# adb.net
KiCad netlist of a schematic drawn in EAGLE
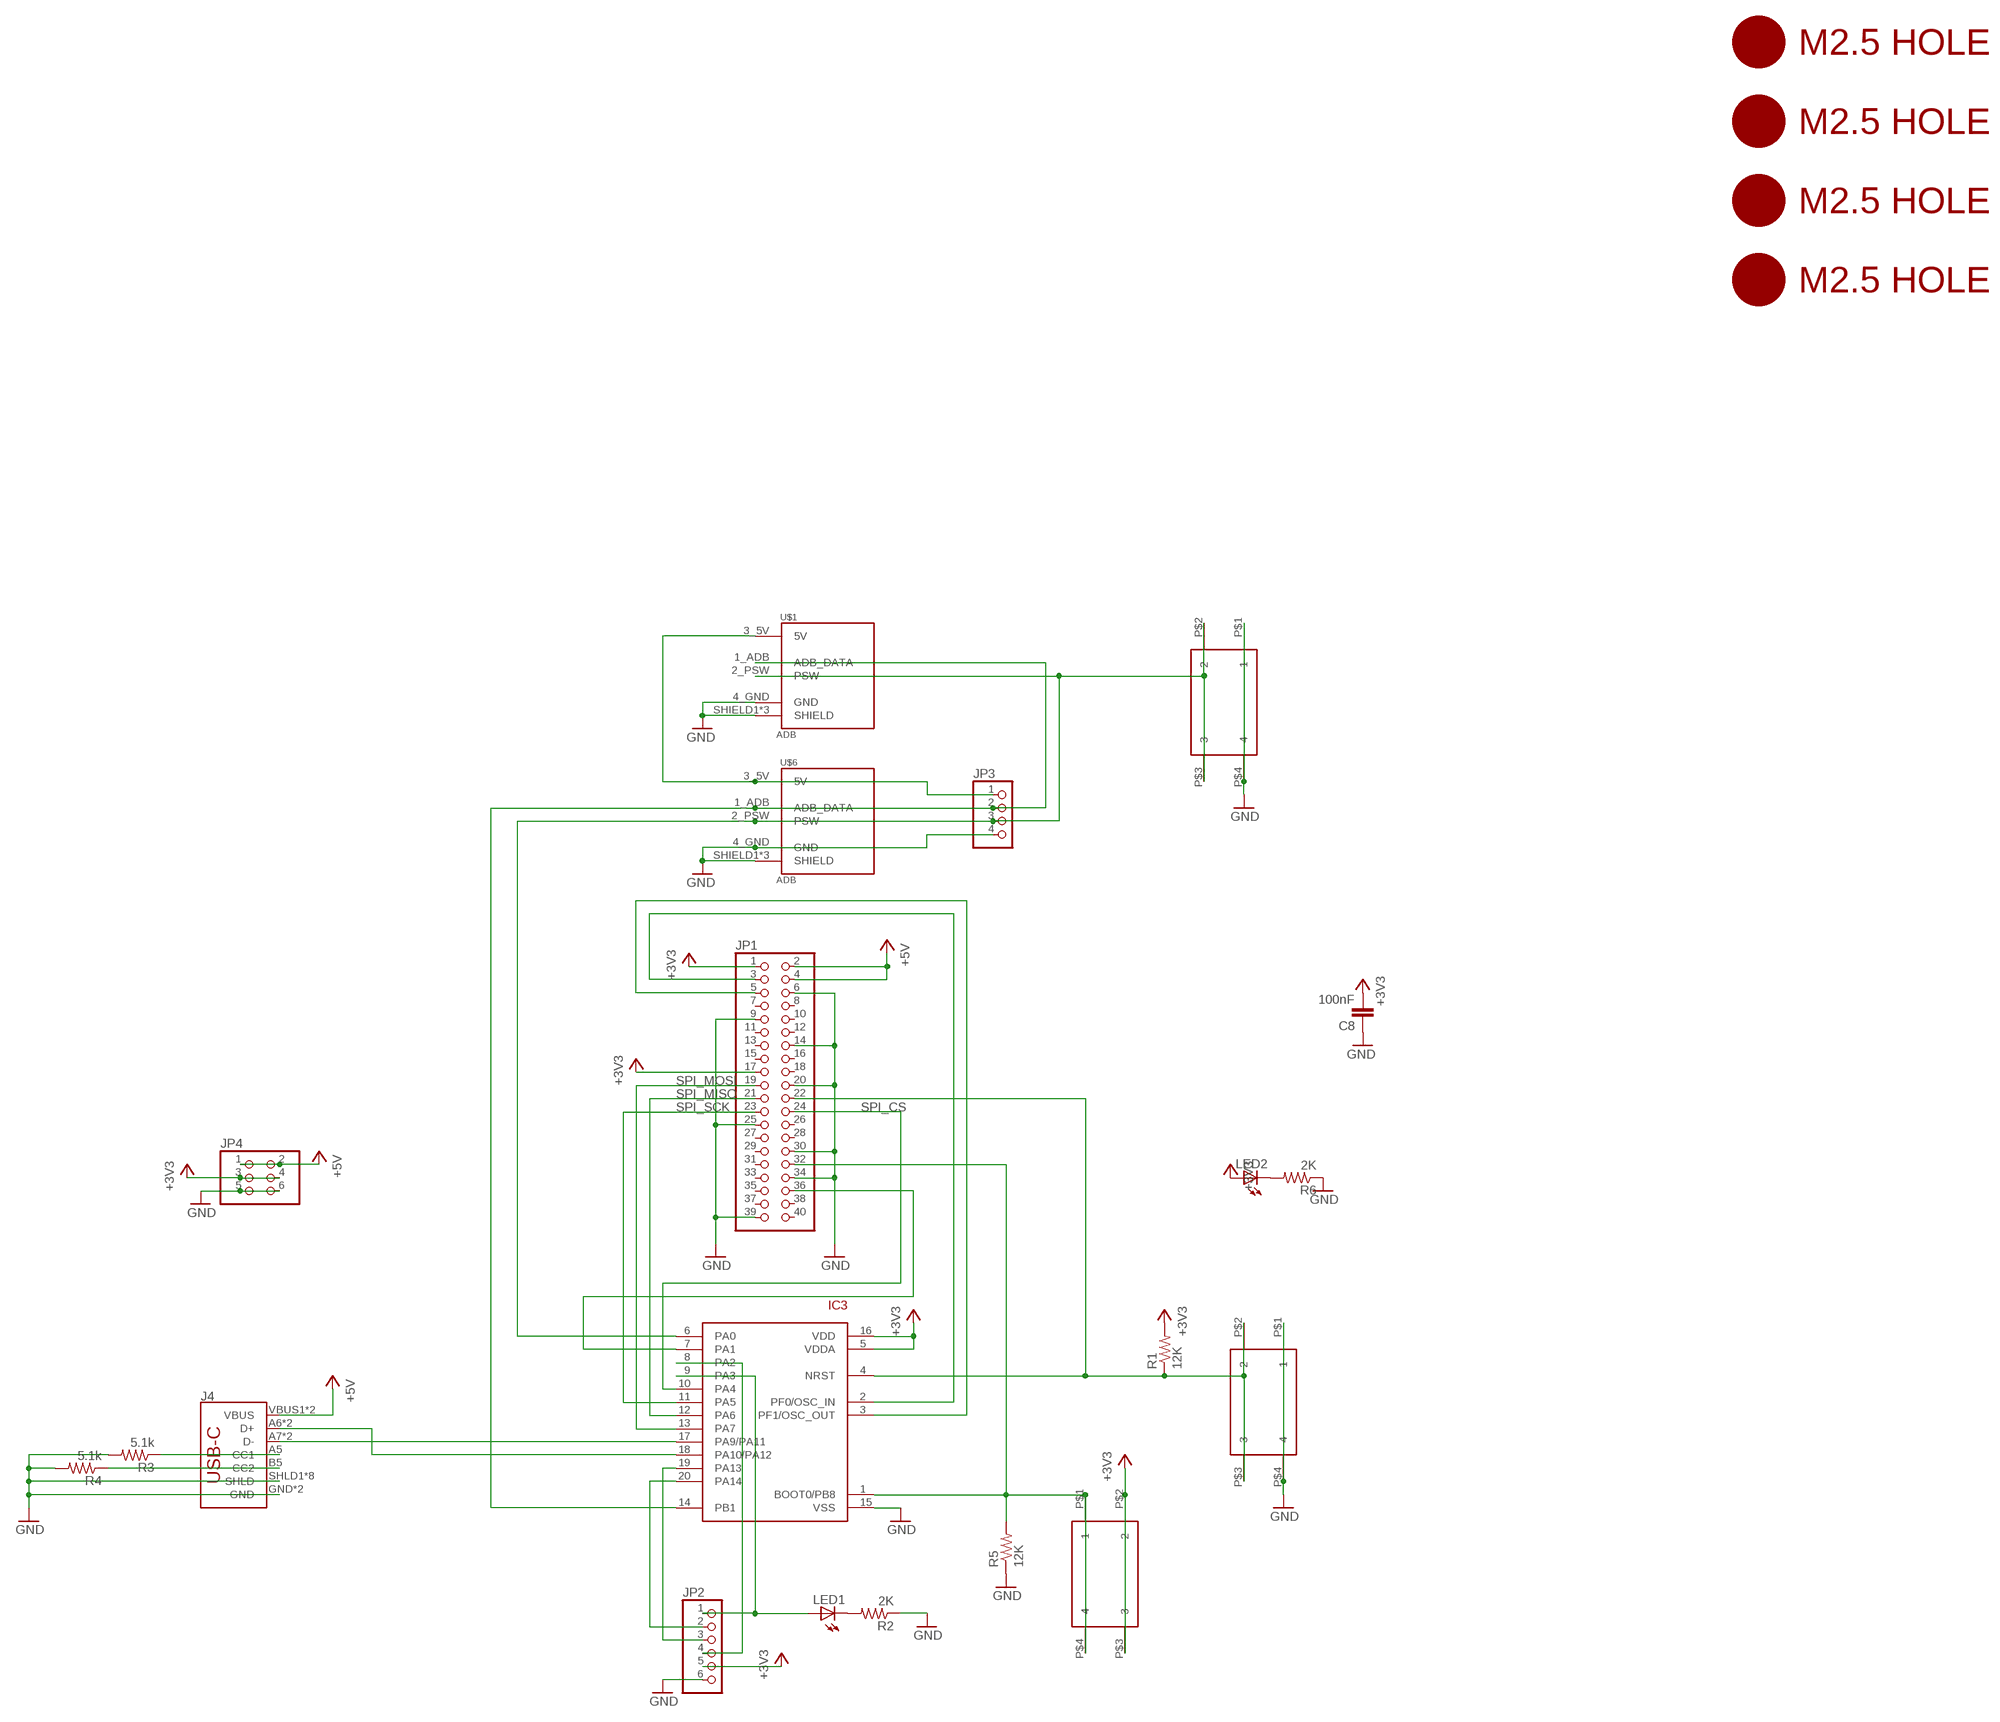
[diagram p0: schematic, sheet 1]

(export (version "E")
  (design (tool "Eeschema 10.0.6"))
  (components
    (comp (ref "C8")
      (value "100nF")
      (footprint "eagle-import:0805@1")
      (libsource (lib "eagle-import") (part "CAP0805"))
    )
    (comp (ref "IC3")
      (value "STM32F042F4")
      (footprint "eagle-import:TSSOP20")
      (libsource (lib "eagle-import") (part "STM32F042F4"))
    )
    (comp (ref "J4")
      (value "USB_C16PIN")
      (footprint "eagle-import:USB-C-16P")
      (libsource (lib "eagle-import") (part "USB_C16PIN"))
    )
    (comp (ref "JP1")
      (value "PINHD-2X20-BIG")
      (footprint "eagle-import:2X20-BIG")
      (libsource (lib "eagle-import") (part "PINHD-2X20-BIG"))
    )
    (comp (ref "JP2")
      (value "PINHD-1X6")
      (footprint "eagle-import:1X06")
      (libsource (lib "eagle-import") (part "PINHD-1X6"))
    )
    (comp (ref "JP3")
      (value "PINHD-1X4")
      (footprint "eagle-import:1X04")
      (libsource (lib "eagle-import") (part "PINHD-1X4"))
    )
    (comp (ref "JP4")
      (value "PINHD-2X3")
      (footprint "eagle-import:2X03")
      (libsource (lib "eagle-import") (part "PINHD-2X3"))
    )
    (comp (ref "LED1")
      (value "LEDCHIP-LED0805")
      (footprint "eagle-import:CHIP-LED0805")
      (libsource (lib "eagle-import") (part "LEDCHIP-LED0805"))
    )
    (comp (ref "LED2")
      (value "LEDCHIP-LED0805")
      (footprint "eagle-import:CHIP-LED0805")
      (libsource (lib "eagle-import") (part "LEDCHIP-LED0805"))
    )
    (comp (ref "R1")
      (value "12K")
      (footprint "eagle-import:0805")
      (libsource (lib "eagle-import") (part "RESISTOR0805-RES"))
    )
    (comp (ref "R2")
      (value "2K")
      (footprint "eagle-import:0805")
      (libsource (lib "eagle-import") (part "RESISTOR0805-RES"))
    )
    (comp (ref "R3")
      (value "5.1k")
      (footprint "eagle-import:0805")
      (libsource (lib "eagle-import") (part "RESISTOR0805-RES"))
    )
    (comp (ref "R4")
      (value "5.1k")
      (footprint "eagle-import:0805")
      (libsource (lib "eagle-import") (part "RESISTOR0805-RES"))
    )
    (comp (ref "R5")
      (value "12K")
      (footprint "eagle-import:0805")
      (libsource (lib "eagle-import") (part "RESISTOR0805-RES"))
    )
    (comp (ref "R6")
      (value "2K")
      (footprint "eagle-import:0805")
      (libsource (lib "eagle-import") (part "RESISTOR0805-RES"))
    )
    (comp (ref "SW1")
      (value "324_SW")
      (footprint "eagle-import:342_SWICH_FOOT")
      (libsource (lib "eagle-import") (part "324_SW"))
    )
    (comp (ref "SW2")
      (value "324_SW")
      (footprint "eagle-import:342_SWICH_FOOT")
      (libsource (lib "eagle-import") (part "324_SW"))
    )
    (comp (ref "SW4")
      (value "324_SW")
      (footprint "eagle-import:342_SWICH_FOOT")
      (libsource (lib "eagle-import") (part "324_SW"))
    )
    (comp (ref "U$1")
      (value "ADB")
      (footprint "eagle-import:DIN4")
      (libsource (lib "eagle-import") (part "ADB"))
    )
    (comp (ref "U$2")
      (value "M2.5HOLE")
      (footprint "eagle-import:M2.5HOLE")
      (libsource (lib "eagle-import") (part "M2.5HOLE"))
    )
    (comp (ref "U$3")
      (value "M2.5HOLE")
      (footprint "eagle-import:M2.5HOLE")
      (libsource (lib "eagle-import") (part "M2.5HOLE"))
    )
    (comp (ref "U$4")
      (value "M2.5HOLE")
      (footprint "eagle-import:M2.5HOLE")
      (libsource (lib "eagle-import") (part "M2.5HOLE"))
    )
    (comp (ref "U$5")
      (value "M2.5HOLE")
      (footprint "eagle-import:M2.5HOLE")
      (libsource (lib "eagle-import") (part "M2.5HOLE"))
    )
    (comp (ref "U$6")
      (value "ADB")
      (footprint "eagle-import:DIN4")
      (libsource (lib "eagle-import") (part "ADB"))
    )
  )
  (nets
    (net (code "1") (name "+3V3") (class "Default")
      (node (ref "C8") (pin "2") (pinfunction "2_2") (pintype "passive"))
      (node (ref "IC3") (pin "16") (pinfunction "VDD_16") (pintype "bidirectional"))
      (node (ref "IC3") (pin "5") (pinfunction "VDDA_5") (pintype "bidirectional"))
      (node (ref "JP1") (pin "1") (pinfunction "1_1") (pintype "passive"))
      (node (ref "JP1") (pin "17") (pinfunction "17_17") (pintype "passive"))
      (node (ref "JP2") (pin "5") (pinfunction "5_5") (pintype "passive"))
      (node (ref "JP4") (pin "3") (pinfunction "3_3") (pintype "passive"))
      (node (ref "JP4") (pin "4") (pinfunction "4_4") (pintype "passive"))
      (node (ref "LED2") (pin "A") (pinfunction "A_A") (pintype "passive"))
      (node (ref "R1") (pin "2") (pinfunction "2_2") (pintype "passive"))
      (node (ref "SW1") (pin "P$2") (pinfunction "2_P$2") (pintype "bidirectional"))
      (node (ref "SW1") (pin "P$3") (pinfunction "3_P$3") (pintype "bidirectional"))
    )
    (net (code "2") (name "+5V") (class "Default")
      (node (ref "J4") (pin "VBUS1") (pinfunction "VBUS_VBUS1") (pintype "bidirectional"))
      (node (ref "J4") (pin "VBUS2") (pinfunction "VBUS_VBUS2") (pintype "bidirectional"))
      (node (ref "JP1") (pin "2") (pinfunction "2_2") (pintype "passive"))
      (node (ref "JP1") (pin "4") (pinfunction "4_4") (pintype "passive"))
      (node (ref "JP4") (pin "1") (pinfunction "1_1") (pintype "passive"))
      (node (ref "JP4") (pin "2") (pinfunction "2_2") (pintype "passive"))
    )
    (net (code "3") (name "/SPI_CS") (class "Default")
      (node (ref "IC3") (pin "10") (pinfunction "PA4_10") (pintype "bidirectional"))
      (node (ref "JP1") (pin "24") (pinfunction "24_24") (pintype "passive"))
    )
    (net (code "4") (name "/SPI_MISO") (class "Default")
      (node (ref "IC3") (pin "12") (pinfunction "PA6_12") (pintype "bidirectional"))
      (node (ref "JP1") (pin "21") (pinfunction "21_21") (pintype "passive"))
    )
    (net (code "5") (name "/SPI_MOSI") (class "Default")
      (node (ref "IC3") (pin "13") (pinfunction "PA7_13") (pintype "bidirectional"))
      (node (ref "JP1") (pin "19") (pinfunction "19_19") (pintype "passive"))
    )
    (net (code "6") (name "/SPI_SCK") (class "Default")
      (node (ref "IC3") (pin "11") (pinfunction "PA5_11") (pintype "bidirectional"))
      (node (ref "JP1") (pin "23") (pinfunction "23_23") (pintype "passive"))
    )
    (net (code "7") (name "GND") (class "Default")
      (node (ref "C8") (pin "1") (pinfunction "1_1") (pintype "passive"))
      (node (ref "IC3") (pin "15") (pinfunction "VSS_15") (pintype "bidirectional"))
      (node (ref "J4") (pin "GND") (pinfunction "GND_GND") (pintype "bidirectional"))
      (node (ref "J4") (pin "GND2") (pinfunction "GND_GND2") (pintype "bidirectional"))
      (node (ref "J4") (pin "SHLD1") (pinfunction "SHLD_SHLD1") (pintype "bidirectional"))
      (node (ref "J4") (pin "SHLD2") (pinfunction "SHLD_SHLD2") (pintype "bidirectional"))
      (node (ref "J4") (pin "SHLD3") (pinfunction "SHLD_SHLD3") (pintype "bidirectional"))
      (node (ref "J4") (pin "SHLD4") (pinfunction "SHLD_SHLD4") (pintype "bidirectional"))
      (node (ref "J4") (pin "SHLD5") (pinfunction "SHLD_SHLD5") (pintype "bidirectional"))
      (node (ref "J4") (pin "SHLD6") (pinfunction "SHLD_SHLD6") (pintype "bidirectional"))
      (node (ref "J4") (pin "SHLD7") (pinfunction "SHLD_SHLD7") (pintype "bidirectional"))
      (node (ref "J4") (pin "SHLD8") (pinfunction "SHLD_SHLD8") (pintype "bidirectional"))
      (node (ref "JP1") (pin "14") (pinfunction "14_14") (pintype "passive"))
      (node (ref "JP1") (pin "20") (pinfunction "20_20") (pintype "passive"))
      (node (ref "JP1") (pin "25") (pinfunction "25_25") (pintype "passive"))
      (node (ref "JP1") (pin "30") (pinfunction "30_30") (pintype "passive"))
      (node (ref "JP1") (pin "34") (pinfunction "34_34") (pintype "passive"))
      (node (ref "JP1") (pin "39") (pinfunction "39_39") (pintype "passive"))
      (node (ref "JP1") (pin "6") (pinfunction "6_6") (pintype "passive"))
      (node (ref "JP1") (pin "9") (pinfunction "9_9") (pintype "passive"))
      (node (ref "JP2") (pin "6") (pinfunction "6_6") (pintype "passive"))
      (node (ref "JP3") (pin "4") (pinfunction "4_4") (pintype "passive"))
      (node (ref "JP4") (pin "5") (pinfunction "5_5") (pintype "passive"))
      (node (ref "JP4") (pin "6") (pinfunction "6_6") (pintype "passive"))
      (node (ref "R2") (pin "1") (pinfunction "1_1") (pintype "passive"))
      (node (ref "R3") (pin "2") (pinfunction "2_2") (pintype "passive"))
      (node (ref "R4") (pin "2") (pinfunction "2_2") (pintype "passive"))
      (node (ref "R5") (pin "1") (pinfunction "1_1") (pintype "passive"))
      (node (ref "R6") (pin "1") (pinfunction "1_1") (pintype "passive"))
      (node (ref "SW2") (pin "P$1") (pinfunction "1_P$1") (pintype "bidirectional"))
      (node (ref "SW2") (pin "P$4") (pinfunction "4_P$4") (pintype "bidirectional"))
      (node (ref "SW4") (pin "P$1") (pinfunction "1_P$1") (pintype "bidirectional"))
      (node (ref "SW4") (pin "P$4") (pinfunction "4_P$4") (pintype "bidirectional"))
      (node (ref "U$1") (pin "4_GND") (pinfunction "GND_4_GND") (pintype "bidirectional"))
      (node (ref "U$1") (pin "SHIELD1") (pinfunction "SHIELD_SHIELD1") (pintype "bidirectional"))
      (node (ref "U$1") (pin "SHIELD2") (pinfunction "SHIELD_SHIELD2") (pintype "bidirectional"))
      (node (ref "U$1") (pin "SHIELD3") (pinfunction "SHIELD_SHIELD3") (pintype "bidirectional"))
      (node (ref "U$6") (pin "4_GND") (pinfunction "GND_4_GND") (pintype "bidirectional"))
      (node (ref "U$6") (pin "SHIELD1") (pinfunction "SHIELD_SHIELD1") (pintype "bidirectional"))
      (node (ref "U$6") (pin "SHIELD2") (pinfunction "SHIELD_SHIELD2") (pintype "bidirectional"))
      (node (ref "U$6") (pin "SHIELD3") (pinfunction "SHIELD_SHIELD3") (pintype "bidirectional"))
    )
    (net (code "8") (name "Net-(IC3-BOOT0{slash}PB8)") (class "Default")
      (node (ref "IC3") (pin "1") (pinfunction "BOOT0/PB8_1") (pintype "bidirectional"))
      (node (ref "JP1") (pin "32") (pinfunction "32_32") (pintype "passive"))
      (node (ref "R5") (pin "2") (pinfunction "2_2") (pintype "passive"))
      (node (ref "SW1") (pin "P$1") (pinfunction "1_P$1") (pintype "bidirectional"))
      (node (ref "SW1") (pin "P$4") (pinfunction "4_P$4") (pintype "bidirectional"))
    )
    (net (code "9") (name "Net-(IC3-NRST)") (class "Default")
      (node (ref "IC3") (pin "4") (pinfunction "NRST_4") (pintype "bidirectional"))
      (node (ref "JP1") (pin "22") (pinfunction "22_22") (pintype "passive"))
      (node (ref "R1") (pin "1") (pinfunction "1_1") (pintype "passive"))
      (node (ref "SW4") (pin "P$2") (pinfunction "2_P$2") (pintype "bidirectional"))
      (node (ref "SW4") (pin "P$3") (pinfunction "3_P$3") (pintype "bidirectional"))
    )
    (net (code "10") (name "Net-(IC3-PA0)") (class "Default")
      (node (ref "IC3") (pin "6") (pinfunction "PA0_6") (pintype "bidirectional"))
      (node (ref "JP3") (pin "3") (pinfunction "3_3") (pintype "passive"))
      (node (ref "SW2") (pin "P$2") (pinfunction "2_P$2") (pintype "bidirectional"))
      (node (ref "SW2") (pin "P$3") (pinfunction "3_P$3") (pintype "bidirectional"))
      (node (ref "U$1") (pin "2_PSW") (pinfunction "PSW_2_PSW") (pintype "bidirectional"))
      (node (ref "U$6") (pin "2_PSW") (pinfunction "PSW_2_PSW") (pintype "bidirectional"))
    )
    (net (code "11") (name "Net-(IC3-PA1)") (class "Default")
      (node (ref "IC3") (pin "7") (pinfunction "PA1_7") (pintype "bidirectional"))
      (node (ref "JP1") (pin "36") (pinfunction "36_36") (pintype "passive"))
    )
    (net (code "12") (name "Net-(IC3-PA2)") (class "Default")
      (node (ref "IC3") (pin "8") (pinfunction "PA2_8") (pintype "bidirectional"))
      (node (ref "JP2") (pin "4") (pinfunction "4_4") (pintype "passive"))
    )
    (net (code "13") (name "Net-(IC3-PA3)") (class "Default")
      (node (ref "IC3") (pin "9") (pinfunction "PA3_9") (pintype "bidirectional"))
      (node (ref "JP2") (pin "1") (pinfunction "1_1") (pintype "passive"))
      (node (ref "LED1") (pin "A") (pinfunction "A_A") (pintype "passive"))
    )
    (net (code "14") (name "Net-(IC3-PA9{slash}PA11)") (class "Default")
      (node (ref "IC3") (pin "17") (pinfunction "PA9/PA11_17") (pintype "bidirectional"))
      (node (ref "J4") (pin "A7") (pinfunction "D-_A7") (pintype "bidirectional"))
      (node (ref "J4") (pin "B7") (pinfunction "D-_B7") (pintype "bidirectional"))
    )
    (net (code "15") (name "Net-(IC3-PA10{slash}PA12)") (class "Default")
      (node (ref "IC3") (pin "18") (pinfunction "PA10/PA12_18") (pintype "bidirectional"))
      (node (ref "J4") (pin "A6") (pinfunction "D+_A6") (pintype "bidirectional"))
      (node (ref "J4") (pin "B6") (pinfunction "D+_B6") (pintype "bidirectional"))
    )
    (net (code "16") (name "Net-(IC3-PA13)") (class "Default")
      (node (ref "IC3") (pin "19") (pinfunction "PA13_19") (pintype "bidirectional"))
      (node (ref "JP2") (pin "3") (pinfunction "3_3") (pintype "passive"))
    )
    (net (code "17") (name "Net-(IC3-PA14)") (class "Default")
      (node (ref "IC3") (pin "20") (pinfunction "PA14_20") (pintype "bidirectional"))
      (node (ref "JP2") (pin "2") (pinfunction "2_2") (pintype "passive"))
    )
    (net (code "18") (name "Net-(IC3-PB1)") (class "Default")
      (node (ref "IC3") (pin "14") (pinfunction "PB1_14") (pintype "bidirectional"))
      (node (ref "JP3") (pin "2") (pinfunction "2_2") (pintype "passive"))
      (node (ref "U$1") (pin "1_ADB") (pinfunction "ADB_DATA_1_ADB") (pintype "bidirectional"))
      (node (ref "U$6") (pin "1_ADB") (pinfunction "ADB_DATA_1_ADB") (pintype "bidirectional"))
    )
    (net (code "19") (name "Net-(IC3-PF0{slash}OSC_IN)") (class "Default")
      (node (ref "IC3") (pin "2") (pinfunction "PF0/OSC_IN_2") (pintype "bidirectional"))
      (node (ref "JP1") (pin "3") (pinfunction "3_3") (pintype "passive"))
    )
    (net (code "20") (name "Net-(IC3-PF1{slash}OSC_OUT)") (class "Default")
      (node (ref "IC3") (pin "3") (pinfunction "PF1/OSC_OUT_3") (pintype "bidirectional"))
      (node (ref "JP1") (pin "5") (pinfunction "5_5") (pintype "passive"))
    )
    (net (code "21") (name "Net-(J4-CC1)") (class "Default")
      (node (ref "J4") (pin "A5") (pinfunction "CC1_A5") (pintype "bidirectional"))
      (node (ref "R3") (pin "1") (pinfunction "1_1") (pintype "passive"))
    )
    (net (code "22") (name "Net-(J4-CC2)") (class "Default")
      (node (ref "J4") (pin "B5") (pinfunction "CC2_B5") (pintype "bidirectional"))
      (node (ref "R4") (pin "1") (pinfunction "1_1") (pintype "passive"))
    )
    (net (code "23") (name "Net-(LED1-PadC)") (class "Default")
      (node (ref "LED1") (pin "C") (pinfunction "C_C") (pintype "passive"))
      (node (ref "R2") (pin "2") (pinfunction "2_2") (pintype "passive"))
    )
    (net (code "24") (name "Net-(LED2-PadC)") (class "Default")
      (node (ref "LED2") (pin "C") (pinfunction "C_C") (pintype "passive"))
      (node (ref "R6") (pin "2") (pinfunction "2_2") (pintype "passive"))
    )
    (net (code "25") (name "Net-(U$1-5V)") (class "Default")
      (node (ref "JP3") (pin "1") (pinfunction "1_1") (pintype "passive"))
      (node (ref "U$1") (pin "3_5V") (pinfunction "5V_3_5V") (pintype "bidirectional"))
      (node (ref "U$6") (pin "3_5V") (pinfunction "5V_3_5V") (pintype "bidirectional"))
    )
    (net (code "26") (name "unconnected-(JP1-Pad7)") (class "Default")
      (node (ref "JP1") (pin "7") (pinfunction "7_7") (pintype "passive"))
    )
    (net (code "27") (name "unconnected-(JP1-Pad8)") (class "Default")
      (node (ref "JP1") (pin "8") (pinfunction "8_8") (pintype "passive"))
    )
    (net (code "28") (name "unconnected-(JP1-Pad10)") (class "Default")
      (node (ref "JP1") (pin "10") (pinfunction "10_10") (pintype "passive"))
    )
    (net (code "29") (name "unconnected-(JP1-Pad11)") (class "Default")
      (node (ref "JP1") (pin "11") (pinfunction "11_11") (pintype "passive"))
    )
    (net (code "30") (name "unconnected-(JP1-Pad12)") (class "Default")
      (node (ref "JP1") (pin "12") (pinfunction "12_12") (pintype "passive"))
    )
    (net (code "31") (name "unconnected-(JP1-Pad13)") (class "Default")
      (node (ref "JP1") (pin "13") (pinfunction "13_13") (pintype "passive"))
    )
    (net (code "32") (name "unconnected-(JP1-Pad15)") (class "Default")
      (node (ref "JP1") (pin "15") (pinfunction "15_15") (pintype "passive"))
    )
    (net (code "33") (name "unconnected-(JP1-Pad16)") (class "Default")
      (node (ref "JP1") (pin "16") (pinfunction "16_16") (pintype "passive"))
    )
    (net (code "34") (name "unconnected-(JP1-Pad18)") (class "Default")
      (node (ref "JP1") (pin "18") (pinfunction "18_18") (pintype "passive"))
    )
    (net (code "35") (name "unconnected-(JP1-Pad26)") (class "Default")
      (node (ref "JP1") (pin "26") (pinfunction "26_26") (pintype "passive"))
    )
    (net (code "36") (name "unconnected-(JP1-Pad27)") (class "Default")
      (node (ref "JP1") (pin "27") (pinfunction "27_27") (pintype "passive"))
    )
    (net (code "37") (name "unconnected-(JP1-Pad28)") (class "Default")
      (node (ref "JP1") (pin "28") (pinfunction "28_28") (pintype "passive"))
    )
    (net (code "38") (name "unconnected-(JP1-Pad29)") (class "Default")
      (node (ref "JP1") (pin "29") (pinfunction "29_29") (pintype "passive"))
    )
    (net (code "39") (name "unconnected-(JP1-Pad31)") (class "Default")
      (node (ref "JP1") (pin "31") (pinfunction "31_31") (pintype "passive"))
    )
    (net (code "40") (name "unconnected-(JP1-Pad33)") (class "Default")
      (node (ref "JP1") (pin "33") (pinfunction "33_33") (pintype "passive"))
    )
    (net (code "41") (name "unconnected-(JP1-Pad35)") (class "Default")
      (node (ref "JP1") (pin "35") (pinfunction "35_35") (pintype "passive"))
    )
    (net (code "42") (name "unconnected-(JP1-Pad37)") (class "Default")
      (node (ref "JP1") (pin "37") (pinfunction "37_37") (pintype "passive"))
    )
    (net (code "43") (name "unconnected-(JP1-Pad38)") (class "Default")
      (node (ref "JP1") (pin "38") (pinfunction "38_38") (pintype "passive"))
    )
    (net (code "44") (name "unconnected-(JP1-Pad40)") (class "Default")
      (node (ref "JP1") (pin "40") (pinfunction "40_40") (pintype "passive"))
    )
  )
)
